# touchpads.net
KiCad netlist of a schematic drawn in Altium Designer
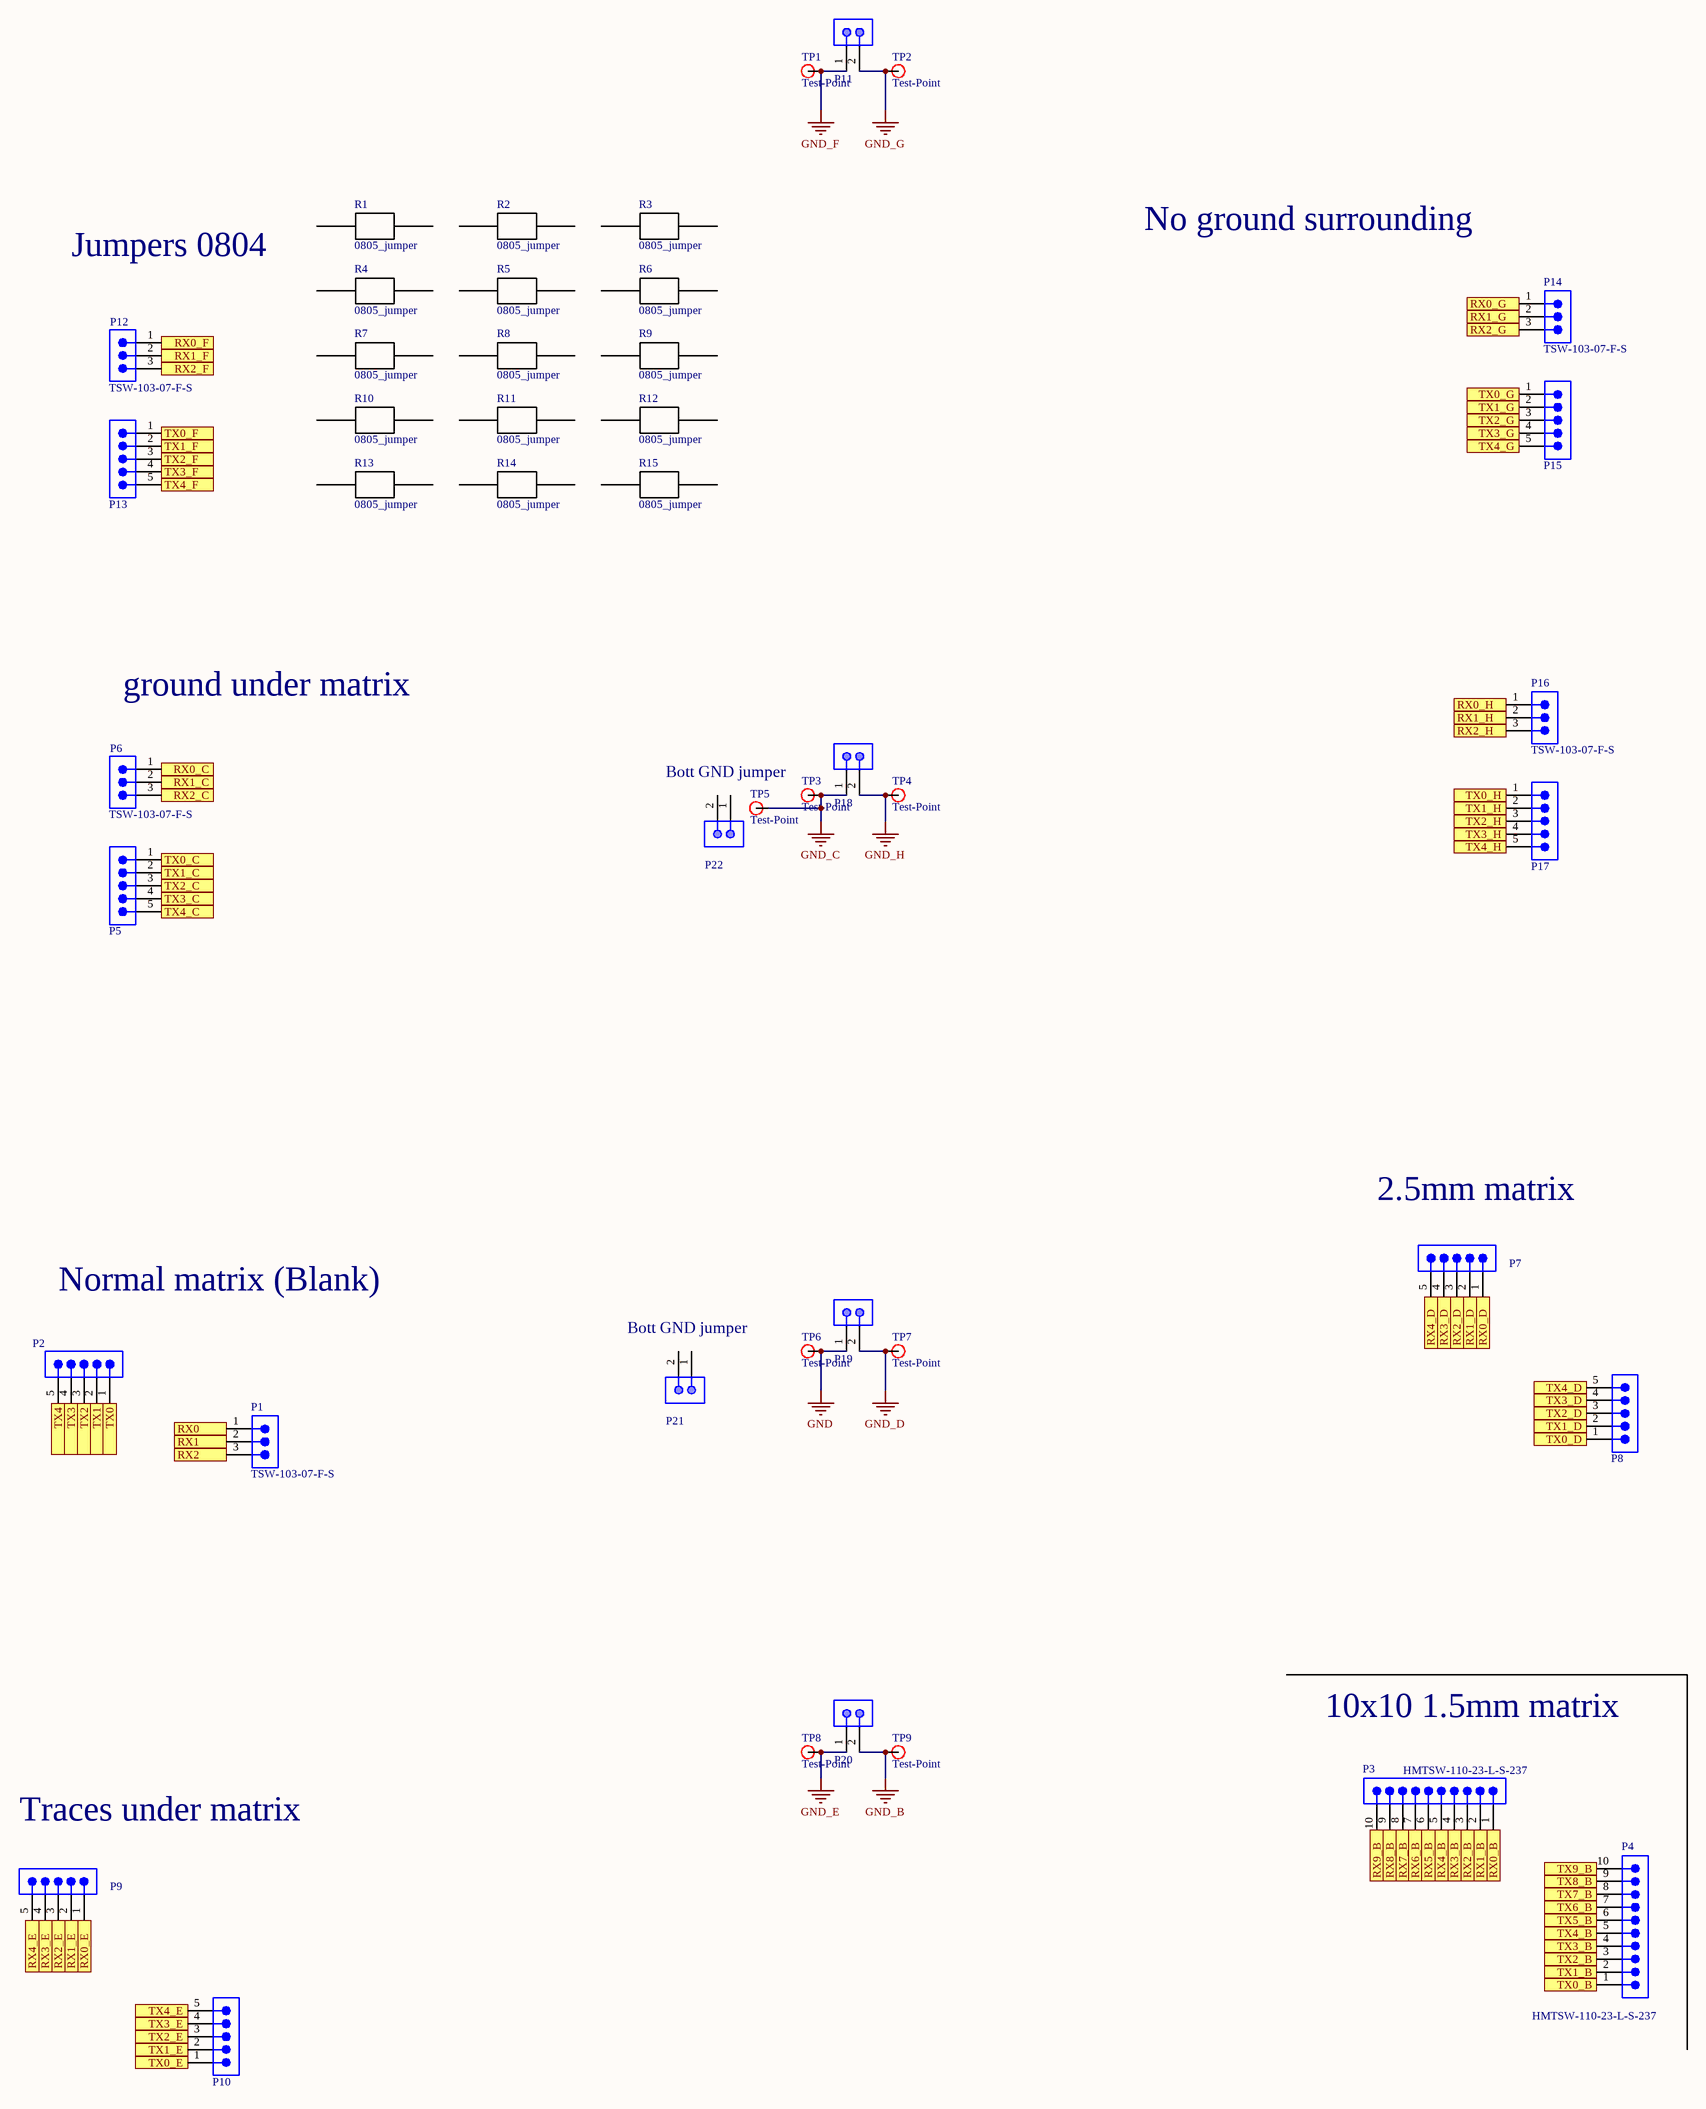
[diagram p0: touchpads.SchDoc]

(export (version "E")
  (design (tool "Eeschema 10.0.6"))
  (components
    (comp (ref "P1")
      (value "TSW-103-07-F-S")
      (footprint "SMTC-TSW-103-07-X-S")
      (description "0.025\" SQ Post Header, Through-hole, Vertical, -55 to 125 degC, 2.54 mm Pitch, 3-Pin, Male, RoHS")
      (fields (field (name "MANUFACTURER") "Samtec"))
      (libsource (lib "Altium Content Vault") (part "SMTC-TSW-103-X-X-S-X"))
    )
    (comp (ref "P2")
      (value "MTLW-105-05-L-S-190")
      (footprint "SMTC-MTLW-105-05-X-S-190")
      (fields (field (name "MANUFACTURER") "Samtec"))
      (libsource (lib "Altium Content Vault") (part "SMTC-MTLW-105-05-X-S-190"))
    )
    (comp (ref "P3")
      (value "HMTSW-110-23-L-S-237")
      (footprint "SMTC-HMTSW-110-23-X-S-237")
      (fields (field (name "MANUFACTURER") "Samtec"))
      (libsource (lib "Altium Content Vault") (part "SMTC-HMTSW-110-23-X-S-237"))
    )
    (comp (ref "P4")
      (value "HMTSW-110-23-L-S-237")
      (footprint "SMTC-HMTSW-110-23-X-S-237")
      (fields (field (name "MANUFACTURER") "Samtec"))
      (libsource (lib "Altium Content Vault") (part "SMTC-HMTSW-110-23-X-S-237"))
    )
    (comp (ref "P5")
      (value "MTLW-105-05-L-S-190")
      (footprint "SMTC-MTLW-105-05-X-S-190")
      (fields (field (name "MANUFACTURER") "Samtec"))
      (libsource (lib "Altium Content Vault") (part "SMTC-MTLW-105-05-X-S-190"))
    )
    (comp (ref "P6")
      (value "TSW-103-07-F-S")
      (footprint "SMTC-TSW-103-07-X-S")
      (description "0.025\" SQ Post Header, Through-hole, Vertical, -55 to 125 degC, 2.54 mm Pitch, 3-Pin, Male, RoHS")
      (fields (field (name "MANUFACTURER") "Samtec"))
      (libsource (lib "Altium Content Vault") (part "SMTC-TSW-103-X-X-S-X"))
    )
    (comp (ref "P7")
      (value "MTLW-105-05-L-S-190")
      (footprint "SMTC-MTLW-105-05-X-S-190")
      (fields (field (name "MANUFACTURER") "Samtec"))
      (libsource (lib "Altium Content Vault") (part "SMTC-MTLW-105-05-X-S-190"))
    )
    (comp (ref "P8")
      (value "MTLW-105-05-L-S-190")
      (footprint "SMTC-MTLW-105-05-X-S-190")
      (fields (field (name "MANUFACTURER") "Samtec"))
      (libsource (lib "Altium Content Vault") (part "SMTC-MTLW-105-05-X-S-190"))
    )
    (comp (ref "P9")
      (value "MTLW-105-05-L-S-190")
      (footprint "SMTC-MTLW-105-05-X-S-190")
      (fields (field (name "MANUFACTURER") "Samtec"))
      (libsource (lib "Altium Content Vault") (part "SMTC-MTLW-105-05-X-S-190"))
    )
    (comp (ref "P10")
      (value "MTLW-105-05-L-S-190")
      (footprint "SMTC-MTLW-105-05-X-S-190")
      (fields (field (name "MANUFACTURER") "Samtec"))
      (libsource (lib "Altium Content Vault") (part "SMTC-MTLW-105-05-X-S-190"))
    )
    (comp (ref "P11")
      (value "613 002 111 21")
      (footprint "WE-61300211121_V")
      (fields (field (name "MANUFACTURER") "Wuerth Elektronik"))
      (libsource (lib "") (part "CN-1P-M-R2_1"))
    )
    (comp (ref "P12")
      (value "TSW-103-07-F-S")
      (footprint "SMTC-TSW-103-07-X-S")
      (description "0.025\" SQ Post Header, Through-hole, Vertical, -55 to 125 degC, 2.54 mm Pitch, 3-Pin, Male, RoHS")
      (fields (field (name "MANUFACTURER") "Samtec"))
      (libsource (lib "Altium Content Vault") (part "SMTC-TSW-103-X-X-S-X"))
    )
    (comp (ref "P13")
      (value "MTLW-105-05-L-S-190")
      (footprint "SMTC-MTLW-105-05-X-S-190")
      (fields (field (name "MANUFACTURER") "Samtec"))
      (libsource (lib "Altium Content Vault") (part "SMTC-MTLW-105-05-X-S-190"))
    )
    (comp (ref "P14")
      (value "TSW-103-07-F-S")
      (footprint "SMTC-TSW-103-07-X-S")
      (description "0.025\" SQ Post Header, Through-hole, Vertical, -55 to 125 degC, 2.54 mm Pitch, 3-Pin, Male, RoHS")
      (fields (field (name "MANUFACTURER") "Samtec"))
      (libsource (lib "Altium Content Vault") (part "SMTC-TSW-103-X-X-S-X"))
    )
    (comp (ref "P15")
      (value "MTLW-105-05-L-S-190")
      (footprint "SMTC-MTLW-105-05-X-S-190")
      (fields (field (name "MANUFACTURER") "Samtec"))
      (libsource (lib "Altium Content Vault") (part "SMTC-MTLW-105-05-X-S-190"))
    )
    (comp (ref "P16")
      (value "TSW-103-07-F-S")
      (footprint "SMTC-TSW-103-07-X-S")
      (description "0.025\" SQ Post Header, Through-hole, Vertical, -55 to 125 degC, 2.54 mm Pitch, 3-Pin, Male, RoHS")
      (fields (field (name "MANUFACTURER") "Samtec"))
      (libsource (lib "Altium Content Vault") (part "SMTC-TSW-103-X-X-S-X"))
    )
    (comp (ref "P17")
      (value "MTLW-105-05-L-S-190")
      (footprint "SMTC-MTLW-105-05-X-S-190")
      (fields (field (name "MANUFACTURER") "Samtec"))
      (libsource (lib "Altium Content Vault") (part "SMTC-MTLW-105-05-X-S-190"))
    )
    (comp (ref "P18")
      (value "613 002 111 21")
      (footprint "WE-61300211121_V")
      (fields (field (name "MANUFACTURER") "Wuerth Elektronik"))
      (libsource (lib "") (part "CN-1P-M-R2_1"))
    )
    (comp (ref "P19")
      (value "613 002 111 21")
      (footprint "WE-61300211121_V")
      (fields (field (name "MANUFACTURER") "Wuerth Elektronik"))
      (libsource (lib "") (part "CN-1P-M-R2_1"))
    )
    (comp (ref "P20")
      (value "613 002 111 21")
      (footprint "WE-61300211121_V")
      (fields (field (name "MANUFACTURER") "Wuerth Elektronik"))
      (libsource (lib "") (part "CN-1P-M-R2_1"))
    )
    (comp (ref "P21")
      (value "613 002 111 21")
      (footprint "WE-61300211121_V")
      (fields (field (name "MANUFACTURER") "Wuerth Elektronik"))
      (libsource (lib "Altium Content Vault") (part "CN-1P-M-R2"))
    )
    (comp (ref "P22")
      (value "613 002 111 21")
      (footprint "WE-61300211121_V")
      (fields (field (name "MANUFACTURER") "Wuerth Elektronik"))
      (libsource (lib "Altium Content Vault") (part "CN-1P-M-R2"))
    )
    (comp (ref "R1")
      (value "0805_jumper")
      (footprint "Resistor")
      (libsource (lib "jumper") (part "0805_jumper"))
    )
    (comp (ref "R2")
      (value "0805_jumper")
      (footprint "Resistor")
      (libsource (lib "jumper") (part "0805_jumper"))
    )
    (comp (ref "R3")
      (value "0805_jumper")
      (footprint "Resistor")
      (libsource (lib "jumper") (part "0805_jumper"))
    )
    (comp (ref "R4")
      (value "0805_jumper")
      (footprint "Resistor")
      (libsource (lib "jumper") (part "0805_jumper"))
    )
    (comp (ref "R5")
      (value "0805_jumper")
      (footprint "Resistor")
      (libsource (lib "jumper") (part "0805_jumper"))
    )
    (comp (ref "R6")
      (value "0805_jumper")
      (footprint "Resistor")
      (libsource (lib "jumper") (part "0805_jumper"))
    )
    (comp (ref "R7")
      (value "0805_jumper")
      (footprint "Resistor")
      (libsource (lib "jumper") (part "0805_jumper"))
    )
    (comp (ref "R8")
      (value "0805_jumper")
      (footprint "Resistor")
      (libsource (lib "jumper") (part "0805_jumper"))
    )
    (comp (ref "R9")
      (value "0805_jumper")
      (footprint "Resistor")
      (libsource (lib "jumper") (part "0805_jumper"))
    )
    (comp (ref "R10")
      (value "0805_jumper")
      (footprint "Resistor")
      (libsource (lib "jumper") (part "0805_jumper"))
    )
    (comp (ref "R11")
      (value "0805_jumper")
      (footprint "Resistor")
      (libsource (lib "jumper") (part "0805_jumper"))
    )
    (comp (ref "R12")
      (value "0805_jumper")
      (footprint "Resistor")
      (libsource (lib "jumper") (part "0805_jumper"))
    )
    (comp (ref "R13")
      (value "0805_jumper")
      (footprint "Resistor")
      (libsource (lib "jumper") (part "0805_jumper"))
    )
    (comp (ref "R14")
      (value "0805_jumper")
      (footprint "Resistor")
      (libsource (lib "jumper") (part "0805_jumper"))
    )
    (comp (ref "R15")
      (value "0805_jumper")
      (footprint "Resistor")
      (libsource (lib "jumper") (part "0805_jumper"))
    )
    (comp (ref "TP1")
      (value "Test-Point")
      (footprint "Test-Point-Footprint-1")
      (description "SMD test pad")
      (libsource (lib "<Company> Vault") (part "Test-Point"))
    )
    (comp (ref "TP2")
      (value "Test-Point")
      (footprint "Test-Point-Footprint-1")
      (description "SMD test pad")
      (libsource (lib "<Company> Vault") (part "Test-Point"))
    )
    (comp (ref "TP3")
      (value "Test-Point")
      (footprint "Test-Point-Footprint-1")
      (description "SMD test pad")
      (libsource (lib "<Company> Vault") (part "Test-Point"))
    )
    (comp (ref "TP4")
      (value "Test-Point")
      (footprint "Test-Point-Footprint-1")
      (description "SMD test pad")
      (libsource (lib "<Company> Vault") (part "Test-Point"))
    )
    (comp (ref "TP5")
      (value "Test-Point")
      (footprint "Test-Point-Footprint-1")
      (description "SMD test pad")
      (libsource (lib "<Company> Vault") (part "Test-Point"))
    )
    (comp (ref "TP6")
      (value "Test-Point")
      (footprint "Test-Point-Footprint-1")
      (description "SMD test pad")
      (libsource (lib "<Company> Vault") (part "Test-Point"))
    )
    (comp (ref "TP7")
      (value "Test-Point")
      (footprint "Test-Point-Footprint-1")
      (description "SMD test pad")
      (libsource (lib "<Company> Vault") (part "Test-Point"))
    )
    (comp (ref "TP8")
      (value "Test-Point")
      (footprint "Test-Point-Footprint-1")
      (description "SMD test pad")
      (libsource (lib "<Company> Vault") (part "Test-Point"))
    )
    (comp (ref "TP9")
      (value "Test-Point")
      (footprint "Test-Point-Footprint-1")
      (description "SMD test pad")
      (libsource (lib "<Company> Vault") (part "Test-Point"))
    )
  )
  (nets
    (net (code "1") (name "/RX0") (class "Default")
      (node (ref "P1") (pin "1") (pinfunction "1_1") (pintype "passive"))
    )
    (net (code "2") (name "/RX0_B") (class "Default")
      (node (ref "P3") (pin "1") (pinfunction "1_1") (pintype "passive"))
    )
    (net (code "3") (name "/RX0_C") (class "Default")
      (node (ref "P6") (pin "1") (pinfunction "1_1") (pintype "passive"))
    )
    (net (code "4") (name "/RX0_D") (class "Default")
      (node (ref "P7") (pin "1") (pinfunction "1_1") (pintype "passive"))
    )
    (net (code "5") (name "/RX0_E") (class "Default")
      (node (ref "P9") (pin "1") (pinfunction "1_1") (pintype "passive"))
    )
    (net (code "6") (name "/RX0_F") (class "Default")
      (node (ref "P12") (pin "1") (pinfunction "1_1") (pintype "passive"))
    )
    (net (code "7") (name "/RX0_G") (class "Default")
      (node (ref "P14") (pin "1") (pinfunction "1_1") (pintype "passive"))
    )
    (net (code "8") (name "/RX0_H") (class "Default")
      (node (ref "P16") (pin "1") (pinfunction "1_1") (pintype "passive"))
    )
    (net (code "9") (name "/RX1") (class "Default")
      (node (ref "P1") (pin "2") (pinfunction "2_2") (pintype "passive"))
    )
    (net (code "10") (name "/RX1_B") (class "Default")
      (node (ref "P3") (pin "2") (pinfunction "2_2") (pintype "passive"))
    )
    (net (code "11") (name "/RX1_C") (class "Default")
      (node (ref "P6") (pin "2") (pinfunction "2_2") (pintype "passive"))
    )
    (net (code "12") (name "/RX1_D") (class "Default")
      (node (ref "P7") (pin "2") (pinfunction "2_2") (pintype "passive"))
    )
    (net (code "13") (name "/RX1_E") (class "Default")
      (node (ref "P9") (pin "2") (pinfunction "2_2") (pintype "passive"))
    )
    (net (code "14") (name "/RX1_F") (class "Default")
      (node (ref "P12") (pin "2") (pinfunction "2_2") (pintype "passive"))
    )
    (net (code "15") (name "/RX1_G") (class "Default")
      (node (ref "P14") (pin "2") (pinfunction "2_2") (pintype "passive"))
    )
    (net (code "16") (name "/RX1_H") (class "Default")
      (node (ref "P16") (pin "2") (pinfunction "2_2") (pintype "passive"))
    )
    (net (code "17") (name "/RX2") (class "Default")
      (node (ref "P1") (pin "3") (pinfunction "3_3") (pintype "passive"))
    )
    (net (code "18") (name "/RX2_B") (class "Default")
      (node (ref "P3") (pin "3") (pinfunction "3_3") (pintype "passive"))
    )
    (net (code "19") (name "/RX2_C") (class "Default")
      (node (ref "P6") (pin "3") (pinfunction "3_3") (pintype "passive"))
    )
    (net (code "20") (name "/RX2_D") (class "Default")
      (node (ref "P7") (pin "3") (pinfunction "3_3") (pintype "passive"))
    )
    (net (code "21") (name "/RX2_E") (class "Default")
      (node (ref "P9") (pin "3") (pinfunction "3_3") (pintype "passive"))
    )
    (net (code "22") (name "/RX2_F") (class "Default")
      (node (ref "P12") (pin "3") (pinfunction "3_3") (pintype "passive"))
    )
    (net (code "23") (name "/RX2_G") (class "Default")
      (node (ref "P14") (pin "3") (pinfunction "3_3") (pintype "passive"))
    )
    (net (code "24") (name "/RX2_H") (class "Default")
      (node (ref "P16") (pin "3") (pinfunction "3_3") (pintype "passive"))
    )
    (net (code "25") (name "/RX3_B") (class "Default")
      (node (ref "P3") (pin "4") (pinfunction "4_4") (pintype "passive"))
    )
    (net (code "26") (name "/RX3_D") (class "Default")
      (node (ref "P7") (pin "4") (pinfunction "4_4") (pintype "passive"))
    )
    (net (code "27") (name "/RX3_E") (class "Default")
      (node (ref "P9") (pin "4") (pinfunction "4_4") (pintype "passive"))
    )
    (net (code "28") (name "/RX4_B") (class "Default")
      (node (ref "P3") (pin "5") (pinfunction "5_5") (pintype "passive"))
    )
    (net (code "29") (name "/RX4_D") (class "Default")
      (node (ref "P7") (pin "5") (pinfunction "5_5") (pintype "passive"))
    )
    (net (code "30") (name "/RX4_E") (class "Default")
      (node (ref "P9") (pin "5") (pinfunction "5_5") (pintype "passive"))
    )
    (net (code "31") (name "/RX5_B") (class "Default")
      (node (ref "P3") (pin "6") (pinfunction "6_6") (pintype "passive"))
    )
    (net (code "32") (name "/RX6_B") (class "Default")
      (node (ref "P3") (pin "7") (pinfunction "7_7") (pintype "passive"))
    )
    (net (code "33") (name "/RX7_B") (class "Default")
      (node (ref "P3") (pin "8") (pinfunction "8_8") (pintype "passive"))
    )
    (net (code "34") (name "/RX8_B") (class "Default")
      (node (ref "P3") (pin "9") (pinfunction "9_9") (pintype "passive"))
    )
    (net (code "35") (name "/RX9_B") (class "Default")
      (node (ref "P3") (pin "10") (pinfunction "10_10") (pintype "passive"))
    )
    (net (code "36") (name "/TX0") (class "Default")
      (node (ref "P2") (pin "1") (pinfunction "1_1") (pintype "passive"))
    )
    (net (code "37") (name "/TX0_B") (class "Default")
      (node (ref "P4") (pin "1") (pinfunction "1_1") (pintype "passive"))
    )
    (net (code "38") (name "/TX0_C") (class "Default")
      (node (ref "P5") (pin "1") (pinfunction "1_1") (pintype "passive"))
    )
    (net (code "39") (name "/TX0_D") (class "Default")
      (node (ref "P8") (pin "1") (pinfunction "1_1") (pintype "passive"))
    )
    (net (code "40") (name "/TX0_E") (class "Default")
      (node (ref "P10") (pin "1") (pinfunction "1_1") (pintype "passive"))
    )
    (net (code "41") (name "/TX0_F") (class "Default")
      (node (ref "P13") (pin "1") (pinfunction "1_1") (pintype "passive"))
    )
    (net (code "42") (name "/TX0_G") (class "Default")
      (node (ref "P15") (pin "1") (pinfunction "1_1") (pintype "passive"))
    )
    (net (code "43") (name "/TX0_H") (class "Default")
      (node (ref "P17") (pin "1") (pinfunction "1_1") (pintype "passive"))
    )
    (net (code "44") (name "/TX1") (class "Default")
      (node (ref "P2") (pin "2") (pinfunction "2_2") (pintype "passive"))
    )
    (net (code "45") (name "/TX1_B") (class "Default")
      (node (ref "P4") (pin "2") (pinfunction "2_2") (pintype "passive"))
    )
    (net (code "46") (name "/TX1_C") (class "Default")
      (node (ref "P5") (pin "2") (pinfunction "2_2") (pintype "passive"))
    )
    (net (code "47") (name "/TX1_D") (class "Default")
      (node (ref "P8") (pin "2") (pinfunction "2_2") (pintype "passive"))
    )
    (net (code "48") (name "/TX1_E") (class "Default")
      (node (ref "P10") (pin "2") (pinfunction "2_2") (pintype "passive"))
    )
    (net (code "49") (name "/TX1_F") (class "Default")
      (node (ref "P13") (pin "2") (pinfunction "2_2") (pintype "passive"))
    )
    (net (code "50") (name "/TX1_G") (class "Default")
      (node (ref "P15") (pin "2") (pinfunction "2_2") (pintype "passive"))
    )
    (net (code "51") (name "/TX1_H") (class "Default")
      (node (ref "P17") (pin "2") (pinfunction "2_2") (pintype "passive"))
    )
    (net (code "52") (name "/TX2") (class "Default")
      (node (ref "P2") (pin "3") (pinfunction "3_3") (pintype "passive"))
    )
    (net (code "53") (name "/TX2_B") (class "Default")
      (node (ref "P4") (pin "3") (pinfunction "3_3") (pintype "passive"))
    )
    (net (code "54") (name "/TX2_C") (class "Default")
      (node (ref "P5") (pin "3") (pinfunction "3_3") (pintype "passive"))
    )
    (net (code "55") (name "/TX2_D") (class "Default")
      (node (ref "P8") (pin "3") (pinfunction "3_3") (pintype "passive"))
    )
    (net (code "56") (name "/TX2_E") (class "Default")
      (node (ref "P10") (pin "3") (pinfunction "3_3") (pintype "passive"))
    )
    (net (code "57") (name "/TX2_F") (class "Default")
      (node (ref "P13") (pin "3") (pinfunction "3_3") (pintype "passive"))
    )
    (net (code "58") (name "/TX2_G") (class "Default")
      (node (ref "P15") (pin "3") (pinfunction "3_3") (pintype "passive"))
    )
    (net (code "59") (name "/TX2_H") (class "Default")
      (node (ref "P17") (pin "3") (pinfunction "3_3") (pintype "passive"))
    )
    (net (code "60") (name "/TX3") (class "Default")
      (node (ref "P2") (pin "4") (pinfunction "4_4") (pintype "passive"))
    )
    (net (code "61") (name "/TX3_B") (class "Default")
      (node (ref "P4") (pin "4") (pinfunction "4_4") (pintype "passive"))
    )
    (net (code "62") (name "/TX3_C") (class "Default")
      (node (ref "P5") (pin "4") (pinfunction "4_4") (pintype "passive"))
    )
    (net (code "63") (name "/TX3_D") (class "Default")
      (node (ref "P8") (pin "4") (pinfunction "4_4") (pintype "passive"))
    )
    (net (code "64") (name "/TX3_E") (class "Default")
      (node (ref "P10") (pin "4") (pinfunction "4_4") (pintype "passive"))
    )
    (net (code "65") (name "/TX3_F") (class "Default")
      (node (ref "P13") (pin "4") (pinfunction "4_4") (pintype "passive"))
    )
    (net (code "66") (name "/TX3_G") (class "Default")
      (node (ref "P15") (pin "4") (pinfunction "4_4") (pintype "passive"))
    )
    (net (code "67") (name "/TX3_H") (class "Default")
      (node (ref "P17") (pin "4") (pinfunction "4_4") (pintype "passive"))
    )
    (net (code "68") (name "/TX4") (class "Default")
      (node (ref "P2") (pin "5") (pinfunction "5_5") (pintype "passive"))
    )
    (net (code "69") (name "/TX4_B") (class "Default")
      (node (ref "P4") (pin "5") (pinfunction "5_5") (pintype "passive"))
    )
    (net (code "70") (name "/TX4_C") (class "Default")
      (node (ref "P5") (pin "5") (pinfunction "5_5") (pintype "passive"))
    )
    (net (code "71") (name "/TX4_D") (class "Default")
      (node (ref "P8") (pin "5") (pinfunction "5_5") (pintype "passive"))
    )
    (net (code "72") (name "/TX4_E") (class "Default")
      (node (ref "P10") (pin "5") (pinfunction "5_5") (pintype "passive"))
    )
    (net (code "73") (name "/TX4_F") (class "Default")
      (node (ref "P13") (pin "5") (pinfunction "5_5") (pintype "passive"))
    )
    (net (code "74") (name "/TX4_G") (class "Default")
      (node (ref "P15") (pin "5") (pinfunction "5_5") (pintype "passive"))
    )
    (net (code "75") (name "/TX4_H") (class "Default")
      (node (ref "P17") (pin "5") (pinfunction "5_5") (pintype "passive"))
    )
    (net (code "76") (name "/TX5_B") (class "Default")
      (node (ref "P4") (pin "6") (pinfunction "6_6") (pintype "passive"))
    )
    (net (code "77") (name "/TX6_B") (class "Default")
      (node (ref "P4") (pin "7") (pinfunction "7_7") (pintype "passive"))
    )
    (net (code "78") (name "/TX7_B") (class "Default")
      (node (ref "P4") (pin "8") (pinfunction "8_8") (pintype "passive"))
    )
    (net (code "79") (name "/TX8_B") (class "Default")
      (node (ref "P4") (pin "9") (pinfunction "9_9") (pintype "passive"))
    )
    (net (code "80") (name "/TX9_B") (class "Default")
      (node (ref "P4") (pin "10") (pinfunction "10_10") (pintype "passive"))
    )
    (net (code "81") (name "GND") (class "Default")
      (node (ref "P19") (pin "1") (pinfunction "1_1") (pintype "passive"))
      (node (ref "TP6") (pin "1") (pinfunction "1_1") (pintype "passive"))
    )
    (net (code "82") (name "GND_B") (class "Default")
      (node (ref "P20") (pin "2") (pinfunction "2_2") (pintype "passive"))
      (node (ref "TP9") (pin "1") (pinfunction "1_1") (pintype "passive"))
    )
    (net (code "83") (name "GND_C") (class "Default")
      (node (ref "P18") (pin "1") (pinfunction "1_1") (pintype "passive"))
      (node (ref "TP3") (pin "1") (pinfunction "1_1") (pintype "passive"))
      (node (ref "TP5") (pin "1") (pinfunction "1_1") (pintype "passive"))
    )
    (net (code "84") (name "GND_D") (class "Default")
      (node (ref "P19") (pin "2") (pinfunction "2_2") (pintype "passive"))
      (node (ref "TP7") (pin "1") (pinfunction "1_1") (pintype "passive"))
    )
    (net (code "85") (name "GND_E") (class "Default")
      (node (ref "P20") (pin "1") (pinfunction "1_1") (pintype "passive"))
      (node (ref "TP8") (pin "1") (pinfunction "1_1") (pintype "passive"))
    )
    (net (code "86") (name "GND_F") (class "Default")
      (node (ref "P11") (pin "1") (pinfunction "1_1") (pintype "passive"))
      (node (ref "TP1") (pin "1") (pinfunction "1_1") (pintype "passive"))
    )
    (net (code "87") (name "GND_G") (class "Default")
      (node (ref "P11") (pin "2") (pinfunction "2_2") (pintype "passive"))
      (node (ref "TP2") (pin "1") (pinfunction "1_1") (pintype "passive"))
    )
    (net (code "88") (name "GND_H") (class "Default")
      (node (ref "P18") (pin "2") (pinfunction "2_2") (pintype "passive"))
      (node (ref "TP4") (pin "1") (pinfunction "1_1") (pintype "passive"))
    )
    (net (code "89") (name "unconnected-(P21-Pad1)") (class "Default")
      (node (ref "P21") (pin "1") (pinfunction "1_1") (pintype "passive"))
    )
    (net (code "90") (name "unconnected-(P21-Pad2)") (class "Default")
      (node (ref "P21") (pin "2") (pinfunction "2_2") (pintype "passive"))
    )
    (net (code "91") (name "unconnected-(P22-Pad1)") (class "Default")
      (node (ref "P22") (pin "1") (pinfunction "1_1") (pintype "passive"))
    )
    (net (code "92") (name "unconnected-(P22-Pad2)") (class "Default")
      (node (ref "P22") (pin "2") (pinfunction "2_2") (pintype "passive"))
    )
    (net (code "93") (name "unconnected-(R1-Pad31)") (class "Default")
      (node (ref "R1") (pin "31") (pinfunction "31_31") (pintype "passive"))
    )
    (net (code "94") (name "unconnected-(R1-Pad32)") (class "Default")
      (node (ref "R1") (pin "32") (pinfunction "32_32") (pintype "passive"))
    )
    (net (code "95") (name "unconnected-(R2-Pad31)") (class "Default")
      (node (ref "R2") (pin "31") (pinfunction "31_31") (pintype "passive"))
    )
    (net (code "96") (name "unconnected-(R2-Pad32)") (class "Default")
      (node (ref "R2") (pin "32") (pinfunction "32_32") (pintype "passive"))
    )
    (net (code "97") (name "unconnected-(R3-Pad31)") (class "Default")
      (node (ref "R3") (pin "31") (pinfunction "31_31") (pintype "passive"))
    )
    (net (code "98") (name "unconnected-(R3-Pad32)") (class "Default")
      (node (ref "R3") (pin "32") (pinfunction "32_32") (pintype "passive"))
    )
    (net (code "99") (name "unconnected-(R4-Pad31)") (class "Default")
      (node (ref "R4") (pin "31") (pinfunction "31_31") (pintype "passive"))
    )
    (net (code "100") (name "unconnected-(R4-Pad32)") (class "Default")
      (node (ref "R4") (pin "32") (pinfunction "32_32") (pintype "passive"))
    )
    (net (code "101") (name "unconnected-(R5-Pad31)") (class "Default")
      (node (ref "R5") (pin "31") (pinfunction "31_31") (pintype "passive"))
    )
    (net (code "102") (name "unconnected-(R5-Pad32)") (class "Default")
      (node (ref "R5") (pin "32") (pinfunction "32_32") (pintype "passive"))
    )
    (net (code "103") (name "unconnected-(R6-Pad31)") (class "Default")
      (node (ref "R6") (pin "31") (pinfunction "31_31") (pintype "passive"))
    )
    (net (code "104") (name "unconnected-(R6-Pad32)") (class "Default")
      (node (ref "R6") (pin "32") (pinfunction "32_32") (pintype "passive"))
    )
    (net (code "105") (name "unconnected-(R7-Pad31)") (class "Default")
      (node (ref "R7") (pin "31") (pinfunction "31_31") (pintype "passive"))
    )
    (net (code "106") (name "unconnected-(R7-Pad32)") (class "Default")
      (node (ref "R7") (pin "32") (pinfunction "32_32") (pintype "passive"))
    )
    (net (code "107") (name "unconnected-(R8-Pad31)") (class "Default")
      (node (ref "R8") (pin "31") (pinfunction "31_31") (pintype "passive"))
    )
    (net (code "108") (name "unconnected-(R8-Pad32)") (class "Default")
      (node (ref "R8") (pin "32") (pinfunction "32_32") (pintype "passive"))
    )
    (net (code "109") (name "unconnected-(R9-Pad31)") (class "Default")
      (node (ref "R9") (pin "31") (pinfunction "31_31") (pintype "passive"))
    )
    (net (code "110") (name "unconnected-(R9-Pad32)") (class "Default")
      (node (ref "R9") (pin "32") (pinfunction "32_32") (pintype "passive"))
    )
    (net (code "111") (name "unconnected-(R10-Pad31)") (class "Default")
      (node (ref "R10") (pin "31") (pinfunction "31_31") (pintype "passive"))
    )
    (net (code "112") (name "unconnected-(R10-Pad32)") (class "Default")
      (node (ref "R10") (pin "32") (pinfunction "32_32") (pintype "passive"))
    )
    (net (code "113") (name "unconnected-(R11-Pad31)") (class "Default")
      (node (ref "R11") (pin "31") (pinfunction "31_31") (pintype "passive"))
    )
    (net (code "114") (name "unconnected-(R11-Pad32)") (class "Default")
      (node (ref "R11") (pin "32") (pinfunction "32_32") (pintype "passive"))
    )
    (net (code "115") (name "unconnected-(R12-Pad31)") (class "Default")
      (node (ref "R12") (pin "31") (pinfunction "31_31") (pintype "passive"))
    )
    (net (code "116") (name "unconnected-(R12-Pad32)") (class "Default")
      (node (ref "R12") (pin "32") (pinfunction "32_32") (pintype "passive"))
    )
    (net (code "117") (name "unconnected-(R13-Pad31)") (class "Default")
      (node (ref "R13") (pin "31") (pinfunction "31_31") (pintype "passive"))
    )
    (net (code "118") (name "unconnected-(R13-Pad32)") (class "Default")
      (node (ref "R13") (pin "32") (pinfunction "32_32") (pintype "passive"))
    )
    (net (code "119") (name "unconnected-(R14-Pad31)") (class "Default")
      (node (ref "R14") (pin "31") (pinfunction "31_31") (pintype "passive"))
    )
    (net (code "120") (name "unconnected-(R14-Pad32)") (class "Default")
      (node (ref "R14") (pin "32") (pinfunction "32_32") (pintype "passive"))
    )
    (net (code "121") (name "unconnected-(R15-Pad31)") (class "Default")
      (node (ref "R15") (pin "31") (pinfunction "31_31") (pintype "passive"))
    )
    (net (code "122") (name "unconnected-(R15-Pad32)") (class "Default")
      (node (ref "R15") (pin "32") (pinfunction "32_32") (pintype "passive"))
    )
  )
)
